# mian.net
KiCad netlist of a schematic drawn in EAGLE
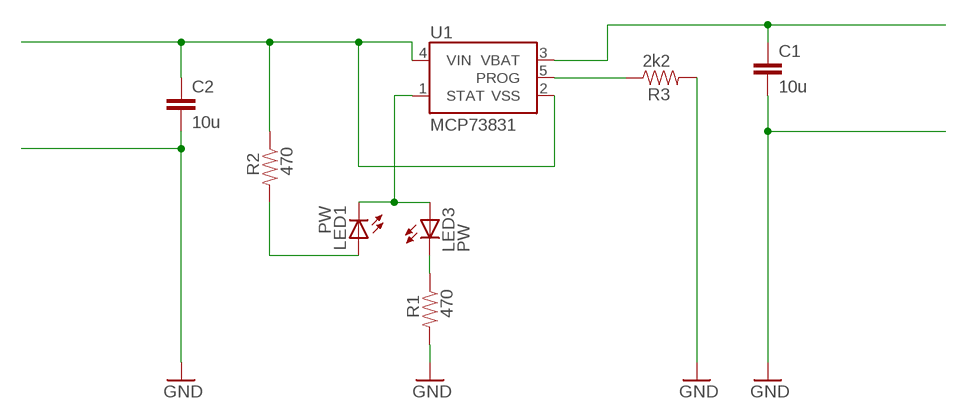
[diagram p0: schematic, sheet 1]

(export (version "E")
  (design (tool "Eeschema 10.0.6"))
  (components
    (comp (ref "C1")
      (value "10u")
      (footprint "eagle-import:0805")
      (libsource (lib "eagle-import") (part "CAP0805"))
    )
    (comp (ref "C2")
      (value "10u")
      (footprint "eagle-import:0805")
      (libsource (lib "eagle-import") (part "CAP0805"))
    )
    (comp (ref "LED1")
      (value "PW")
      (footprint "eagle-import:LED3MM")
      (libsource (lib "eagle-import") (part "LED3MM"))
    )
    (comp (ref "LED3")
      (value "PW")
      (footprint "eagle-import:LED3MM")
      (libsource (lib "eagle-import") (part "LED3MM"))
    )
    (comp (ref "R1")
      (value "470")
      (footprint "eagle-import:0805")
      (libsource (lib "eagle-import") (part "RESISTOR0805-RES"))
    )
    (comp (ref "R2")
      (value "470")
      (footprint "eagle-import:0805")
      (libsource (lib "eagle-import") (part "RESISTOR0805-RES"))
    )
    (comp (ref "R3")
      (value "2k2")
      (footprint "eagle-import:0805")
      (libsource (lib "eagle-import") (part "RESISTOR0805-RES"))
    )
    (comp (ref "U1")
      (value "MCP73831")
      (footprint "eagle-import:SOT23-5")
      (libsource (lib "eagle-import") (part "MCP73831"))
    )
  )
  (nets
    (net (code "1") (name "GND") (class "Default")
      (node (ref "C1") (pin "2") (pinfunction "2_2") (pintype "passive"))
      (node (ref "C2") (pin "2") (pinfunction "2_2") (pintype "passive"))
      (node (ref "R1") (pin "2") (pinfunction "2_2") (pintype "passive"))
      (node (ref "R3") (pin "2") (pinfunction "2_2") (pintype "passive"))
    )
    (net (code "2") (name "Net-(LED1-C)") (class "Default")
      (node (ref "LED1") (pin "K") (pinfunction "C_K") (pintype "passive"))
      (node (ref "LED3") (pin "A") (pinfunction "A_A") (pintype "passive"))
      (node (ref "U1") (pin "1") (pinfunction "STAT_1") (pintype "output"))
    )
    (net (code "3") (name "Net-(LED1-PadA)") (class "Default")
      (node (ref "LED1") (pin "A") (pinfunction "A_A") (pintype "passive"))
      (node (ref "R2") (pin "2") (pinfunction "2_2") (pintype "passive"))
    )
    (net (code "4") (name "Net-(LED3-C)") (class "Default")
      (node (ref "LED3") (pin "K") (pinfunction "C_K") (pintype "passive"))
      (node (ref "R1") (pin "1") (pinfunction "1_1") (pintype "passive"))
    )
    (net (code "5") (name "Net-(U1-PROG)") (class "Default")
      (node (ref "R3") (pin "1") (pinfunction "1_1") (pintype "passive"))
      (node (ref "U1") (pin "5") (pinfunction "PROG_5") (pintype "input"))
    )
    (net (code "6") (name "Net-(U1-VBAT)") (class "Default")
      (node (ref "C1") (pin "1") (pinfunction "1_1") (pintype "passive"))
      (node (ref "U1") (pin "3") (pinfunction "VBAT_3") (pintype "power_in"))
    )
    (net (code "7") (name "Net-(U1-VIN)") (class "Default")
      (node (ref "C2") (pin "1") (pinfunction "1_1") (pintype "passive"))
      (node (ref "R2") (pin "1") (pinfunction "1_1") (pintype "passive"))
      (node (ref "U1") (pin "2") (pinfunction "VSS_2") (pintype "power_in"))
      (node (ref "U1") (pin "4") (pinfunction "VIN_4") (pintype "power_in"))
    )
  )
)
